# 1.net
KiCad netlist of a schematic drawn in Altium Designer
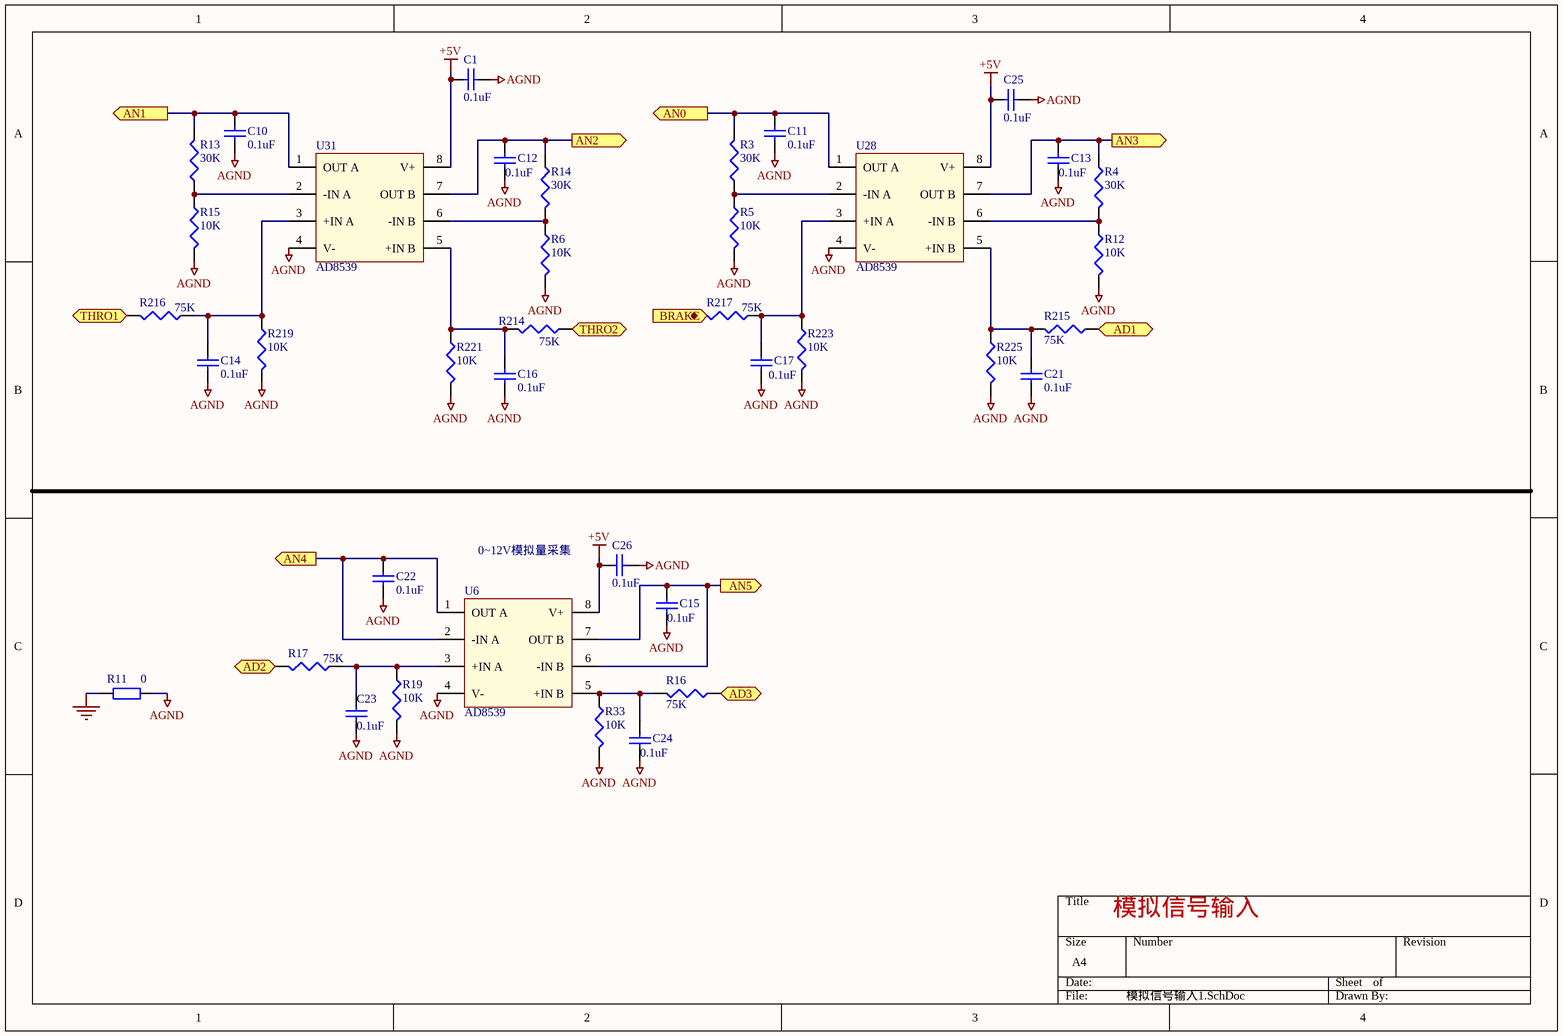
[diagram p0: 模拟信号输入1.SchDoc]

(export (version "E")
  (design (tool "Eeschema 10.0.6"))
  (components
    (comp (ref "C1")
      (value "0.1uF")
      (footprint "0603-L")
      (description "Ceramic, X7R, 100V, 10%, 0603")
      (fields (field (name "Comment") "Cap") (field (name "PUBLISHER") "Altium Limited"))
      (libsource (lib "Resistor") (part "CC0603KRX7R0BB104"))
    )
    (comp (ref "C10")
      (value "0.1uF")
      (footprint "0603-L")
      (description "Capacitor")
      (fields (field (name "Comment") "Cap") (field (name "PUBLISHER") "Altium Limited"))
      (libsource (lib "Miscellaneous Devices") (part "Cap"))
    )
    (comp (ref "C11")
      (value "0.1uF")
      (footprint "0603-L")
      (description "Capacitor")
      (fields (field (name "Comment") "Cap") (field (name "PUBLISHER") "Altium Limited"))
      (libsource (lib "Miscellaneous Devices") (part "Cap"))
    )
    (comp (ref "C12")
      (value "0.1uF")
      (footprint "0603-L")
      (description "Capacitor")
      (fields (field (name "Comment") "Cap") (field (name "PUBLISHER") "Altium Limited"))
      (libsource (lib "Miscellaneous Devices") (part "Cap"))
    )
    (comp (ref "C13")
      (value "0.1uF")
      (footprint "0603-L")
      (description "Capacitor")
      (fields (field (name "Comment") "Cap") (field (name "PUBLISHER") "Altium Limited"))
      (libsource (lib "Miscellaneous Devices") (part "Cap"))
    )
    (comp (ref "C14")
      (value "0.1uF")
      (footprint "0603-L")
      (description "Capacitor")
      (fields (field (name "Comment") "Cap") (field (name "PUBLISHER") "Altium Limited"))
      (libsource (lib "Miscellaneous Devices") (part "Cap"))
    )
    (comp (ref "C15")
      (value "0.1uF")
      (footprint "0603-L")
      (description "Capacitor")
      (fields (field (name "Comment") "Cap") (field (name "PUBLISHER") "Altium Limited"))
      (libsource (lib "Miscellaneous Devices") (part "Cap"))
    )
    (comp (ref "C16")
      (value "0.1uF")
      (footprint "0603-L")
      (description "Capacitor")
      (fields (field (name "Comment") "Cap") (field (name "PUBLISHER") "Altium Limited"))
      (libsource (lib "Miscellaneous Devices") (part "Cap"))
    )
    (comp (ref "C17")
      (value "0.1uF")
      (footprint "0603-L")
      (description "Capacitor")
      (fields (field (name "Comment") "Cap") (field (name "PUBLISHER") "Altium Limited"))
      (libsource (lib "Miscellaneous Devices") (part "Cap"))
    )
    (comp (ref "C21")
      (value "0.1uF")
      (footprint "0603-L")
      (description "Capacitor")
      (fields (field (name "Comment") "Cap") (field (name "PUBLISHER") "Altium Limited"))
      (libsource (lib "Miscellaneous Devices") (part "Cap"))
    )
    (comp (ref "C22")
      (value "0.1uF")
      (footprint "0603-L")
      (description "Capacitor")
      (fields (field (name "Comment") "Cap") (field (name "PUBLISHER") "Altium Limited"))
      (libsource (lib "Miscellaneous Devices") (part "Cap"))
    )
    (comp (ref "C23")
      (value "0.1uF")
      (footprint "0603-L")
      (description "Capacitor")
      (fields (field (name "Comment") "Cap") (field (name "PUBLISHER") "Altium Limited"))
      (libsource (lib "Miscellaneous Devices") (part "Cap"))
    )
    (comp (ref "C24")
      (value "0.1uF")
      (footprint "0603-L")
      (description "Capacitor")
      (fields (field (name "Comment") "Cap") (field (name "PUBLISHER") "Altium Limited"))
      (libsource (lib "Miscellaneous Devices") (part "Cap"))
    )
    (comp (ref "C25")
      (value "0.1uF")
      (footprint "0603-L")
      (description "Ceramic, X7R, 100V, 10%, 0603")
      (fields (field (name "Comment") "Cap") (field (name "PUBLISHER") "Altium Limited"))
      (libsource (lib "Resistor") (part "CC0603KRX7R0BB104"))
    )
    (comp (ref "C26")
      (value "0.1uF")
      (footprint "0603-L")
      (description "Ceramic, X7R, 100V, 10%, 0603")
      (fields (field (name "Comment") "Cap") (field (name "PUBLISHER") "Altium Limited"))
      (libsource (lib "Resistor") (part "CC0603KRX7R0BB104"))
    )
    (comp (ref "R3")
      (value "30K")
      (footprint "0603-L")
      (description "Resistor")
      (fields (field (name "Comment") "Res3") (field (name "PUBLISHER") "Altium Limited"))
      (libsource (lib "Miscellaneous Devices") (part "Res3"))
    )
    (comp (ref "R4")
      (value "30K")
      (footprint "0603-L")
      (description "Resistor")
      (fields (field (name "Comment") "Res3") (field (name "PUBLISHER") "Altium Limited"))
      (libsource (lib "Miscellaneous Devices") (part "Res3"))
    )
    (comp (ref "R5")
      (value "10K")
      (footprint "0603-L")
      (description "Resistor")
      (fields (field (name "Comment") "Res3") (field (name "PUBLISHER") "Altium Limited"))
      (libsource (lib "Miscellaneous Devices") (part "Res3"))
    )
    (comp (ref "R6")
      (value "10K")
      (footprint "0603-L")
      (description "Resistor")
      (fields (field (name "Comment") "Res3") (field (name "PUBLISHER") "Altium Limited"))
      (libsource (lib "Miscellaneous Devices") (part "Res3"))
    )
    (comp (ref "R11")
      (value "0")
      (footprint "RES1206")
      (description "Resistor")
      (fields (field (name "Comment") "Res2") (field (name "PUBLISHER") "Altium Limited"))
      (libsource (lib "Miscellaneous Devices") (part "Res2"))
    )
    (comp (ref "R12")
      (value "10K")
      (footprint "0603-L")
      (description "Resistor")
      (fields (field (name "Comment") "Res3") (field (name "PUBLISHER") "Altium Limited"))
      (libsource (lib "Miscellaneous Devices") (part "Res3"))
    )
    (comp (ref "R13")
      (value "30K")
      (footprint "0603-L")
      (description "Resistor")
      (fields (field (name "Comment") "Res3") (field (name "PUBLISHER") "Altium Limited"))
      (libsource (lib "Miscellaneous Devices") (part "Res3"))
    )
    (comp (ref "R14")
      (value "30K")
      (footprint "0603-L")
      (description "Resistor")
      (fields (field (name "Comment") "Res3") (field (name "PUBLISHER") "Altium Limited"))
      (libsource (lib "Miscellaneous Devices") (part "Res3"))
    )
    (comp (ref "R15")
      (value "10K")
      (footprint "0603-L")
      (description "Resistor")
      (fields (field (name "Comment") "Res3") (field (name "PUBLISHER") "Altium Limited"))
      (libsource (lib "Miscellaneous Devices") (part "Res3"))
    )
    (comp (ref "R16")
      (value "75K")
      (footprint "0603-L")
      (description "Resistor")
      (fields (field (name "Comment") "Res3") (field (name "PUBLISHER") "Altium Limited"))
      (libsource (lib "Miscellaneous Devices") (part "Res3"))
    )
    (comp (ref "R17")
      (value "75K")
      (footprint "0603-L")
      (description "Resistor")
      (fields (field (name "Comment") "Res3") (field (name "PUBLISHER") "Altium Limited"))
      (libsource (lib "Miscellaneous Devices") (part "Res3"))
    )
    (comp (ref "R19")
      (value "10K")
      (footprint "0603-L")
      (description "Resistor")
      (fields (field (name "Comment") "Res3") (field (name "PUBLISHER") "Altium Limited"))
      (libsource (lib "Miscellaneous Devices") (part "Res3"))
    )
    (comp (ref "R33")
      (value "10K")
      (footprint "0603-L")
      (description "Resistor")
      (fields (field (name "Comment") "Res3") (field (name "PUBLISHER") "Altium Limited"))
      (libsource (lib "Miscellaneous Devices") (part "Res3"))
    )
    (comp (ref "R214")
      (value "75K")
      (footprint "0603-L")
      (description "Resistor")
      (fields (field (name "Comment") "Res3") (field (name "PUBLISHER") "Altium Limited"))
      (libsource (lib "Miscellaneous Devices") (part "Res3"))
    )
    (comp (ref "R215")
      (value "75K")
      (footprint "0603-L")
      (description "Resistor")
      (fields (field (name "Comment") "Res3") (field (name "PUBLISHER") "Altium Limited"))
      (libsource (lib "Miscellaneous Devices") (part "Res3"))
    )
    (comp (ref "R216")
      (value "75K")
      (footprint "0603-L")
      (description "Resistor")
      (fields (field (name "Comment") "Res3") (field (name "PUBLISHER") "Altium Limited"))
      (libsource (lib "Miscellaneous Devices") (part "Res3"))
    )
    (comp (ref "R217")
      (value "75K")
      (footprint "0603-L")
      (description "Resistor")
      (fields (field (name "Comment") "Res3") (field (name "PUBLISHER") "Altium Limited"))
      (libsource (lib "Miscellaneous Devices") (part "Res3"))
    )
    (comp (ref "R219")
      (value "10K")
      (footprint "0603-L")
      (description "Resistor")
      (fields (field (name "Comment") "Res3") (field (name "PUBLISHER") "Altium Limited"))
      (libsource (lib "Miscellaneous Devices") (part "Res3"))
    )
    (comp (ref "R221")
      (value "10K")
      (footprint "0603-L")
      (description "Resistor")
      (fields (field (name "Comment") "Res3") (field (name "PUBLISHER") "Altium Limited"))
      (libsource (lib "Miscellaneous Devices") (part "Res3"))
    )
    (comp (ref "R223")
      (value "10K")
      (footprint "0603-L")
      (description "Resistor")
      (fields (field (name "Comment") "Res3") (field (name "PUBLISHER") "Altium Limited"))
      (libsource (lib "Miscellaneous Devices") (part "Res3"))
    )
    (comp (ref "R225")
      (value "10K")
      (footprint "0603-L")
      (description "Resistor")
      (fields (field (name "Comment") "Res3") (field (name "PUBLISHER") "Altium Limited"))
      (libsource (lib "Miscellaneous Devices") (part "Res3"))
    )
    (comp (ref "U6") (value "AD8539") (footprint "整车控制器:AD8539") (libsource (lib "整车控制器") (part "AD8539")))
    (comp (ref "U28") (value "AD8539") (footprint "整车控制器:AD8539") (libsource (lib "整车控制器") (part "AD8539")))
    (comp (ref "U31") (value "AD8539") (footprint "AD8539") (libsource (lib "整车控制器") (part "AD8539")))
  )
  (nets
    (net (code "1") (name "+5V") (class "Default")
      (node (ref "C1") (pin "2") (pinfunction "2_2") (pintype "passive"))
      (node (ref "C25") (pin "2") (pinfunction "2_2") (pintype "passive"))
      (node (ref "C26") (pin "2") (pinfunction "2_2") (pintype "passive"))
      (node (ref "U28") (pin "8") (pinfunction "V+_8") (pintype "passive"))
      (node (ref "U31") (pin "8") (pinfunction "V+_8") (pintype "passive"))
      (node (ref "U6") (pin "8") (pinfunction "V+_8") (pintype "passive"))
    )
    (net (code "2") (name "/AD1") (class "Default")
      (node (ref "R215") (pin "2") (pinfunction "2_2") (pintype "passive"))
    )
    (net (code "3") (name "/AD2") (class "Default")
      (node (ref "R17") (pin "2") (pinfunction "2_2") (pintype "passive"))
    )
    (net (code "4") (name "/AD3") (class "Default")
      (node (ref "R16") (pin "2") (pinfunction "2_2") (pintype "passive"))
    )
    (net (code "5") (name "/AN0") (class "Default")
      (node (ref "C11") (pin "2") (pinfunction "2_2") (pintype "passive"))
      (node (ref "R3") (pin "2") (pinfunction "2_2") (pintype "passive"))
      (node (ref "U28") (pin "1") (pinfunction "OUT_A_1") (pintype "passive"))
    )
    (net (code "6") (name "/AN1") (class "Default")
      (node (ref "C10") (pin "2") (pinfunction "2_2") (pintype "passive"))
      (node (ref "R13") (pin "2") (pinfunction "2_2") (pintype "passive"))
      (node (ref "U31") (pin "1") (pinfunction "OUT_A_1") (pintype "passive"))
    )
    (net (code "7") (name "/AN2") (class "Default")
      (node (ref "C12") (pin "1") (pinfunction "1_1") (pintype "passive"))
      (node (ref "R14") (pin "1") (pinfunction "1_1") (pintype "passive"))
      (node (ref "U31") (pin "7") (pinfunction "OUT_B_7") (pintype "passive"))
    )
    (net (code "8") (name "/AN3") (class "Default")
      (node (ref "C13") (pin "1") (pinfunction "1_1") (pintype "passive"))
      (node (ref "R4") (pin "1") (pinfunction "1_1") (pintype "passive"))
      (node (ref "U28") (pin "7") (pinfunction "OUT_B_7") (pintype "passive"))
    )
    (net (code "9") (name "/AN4") (class "Default")
      (node (ref "C22") (pin "2") (pinfunction "2_2") (pintype "passive"))
      (node (ref "U6") (pin "1") (pinfunction "OUT_A_1") (pintype "passive"))
      (node (ref "U6") (pin "2") (pinfunction "-IN_A_2") (pintype "passive"))
    )
    (net (code "10") (name "/AN5") (class "Default")
      (node (ref "C15") (pin "1") (pinfunction "1_1") (pintype "passive"))
      (node (ref "U6") (pin "6") (pinfunction "-IN_B_6") (pintype "passive"))
      (node (ref "U6") (pin "7") (pinfunction "OUT_B_7") (pintype "passive"))
    )
    (net (code "11") (name "/BRAKE") (class "Default")
      (node (ref "R217") (pin "2") (pinfunction "2_2") (pintype "passive"))
    )
    (net (code "12") (name "/THRO1") (class "Default")
      (node (ref "R216") (pin "2") (pinfunction "2_2") (pintype "passive"))
    )
    (net (code "13") (name "/THRO2") (class "Default")
      (node (ref "R214") (pin "2") (pinfunction "2_2") (pintype "passive"))
    )
    (net (code "14") (name "AGND") (class "Default")
      (node (ref "C1") (pin "1") (pinfunction "1_1") (pintype "passive"))
      (node (ref "C10") (pin "1") (pinfunction "1_1") (pintype "passive"))
      (node (ref "C11") (pin "1") (pinfunction "1_1") (pintype "passive"))
      (node (ref "C12") (pin "2") (pinfunction "2_2") (pintype "passive"))
      (node (ref "C13") (pin "2") (pinfunction "2_2") (pintype "passive"))
      (node (ref "C14") (pin "1") (pinfunction "1_1") (pintype "passive"))
      (node (ref "C15") (pin "2") (pinfunction "2_2") (pintype "passive"))
      (node (ref "C16") (pin "1") (pinfunction "1_1") (pintype "passive"))
      (node (ref "C17") (pin "1") (pinfunction "1_1") (pintype "passive"))
      (node (ref "C21") (pin "1") (pinfunction "1_1") (pintype "passive"))
      (node (ref "C22") (pin "1") (pinfunction "1_1") (pintype "passive"))
      (node (ref "C23") (pin "1") (pinfunction "1_1") (pintype "passive"))
      (node (ref "C24") (pin "1") (pinfunction "1_1") (pintype "passive"))
      (node (ref "C25") (pin "1") (pinfunction "1_1") (pintype "passive"))
      (node (ref "C26") (pin "1") (pinfunction "1_1") (pintype "passive"))
      (node (ref "R11") (pin "2") (pinfunction "2_2") (pintype "passive"))
      (node (ref "R12") (pin "2") (pinfunction "2_2") (pintype "passive"))
      (node (ref "R15") (pin "2") (pinfunction "2_2") (pintype "passive"))
      (node (ref "R19") (pin "2") (pinfunction "2_2") (pintype "passive"))
      (node (ref "R219") (pin "2") (pinfunction "2_2") (pintype "passive"))
      (node (ref "R221") (pin "2") (pinfunction "2_2") (pintype "passive"))
      (node (ref "R223") (pin "2") (pinfunction "2_2") (pintype "passive"))
      (node (ref "R225") (pin "2") (pinfunction "2_2") (pintype "passive"))
      (node (ref "R33") (pin "2") (pinfunction "2_2") (pintype "passive"))
      (node (ref "R5") (pin "2") (pinfunction "2_2") (pintype "passive"))
      (node (ref "R6") (pin "2") (pinfunction "2_2") (pintype "passive"))
      (node (ref "U28") (pin "4") (pinfunction "V-_4") (pintype "passive"))
      (node (ref "U31") (pin "4") (pinfunction "V-_4") (pintype "passive"))
      (node (ref "U6") (pin "4") (pinfunction "V-_4") (pintype "passive"))
    )
    (net (code "15") (name "GND") (class "Default")
      (node (ref "R11") (pin "1") (pinfunction "1_1") (pintype "passive"))
    )
    (net (code "16") (name "Net-(U6-+IN_A)") (class "Default")
      (node (ref "C23") (pin "2") (pinfunction "2_2") (pintype "passive"))
      (node (ref "R17") (pin "1") (pinfunction "1_1") (pintype "passive"))
      (node (ref "R19") (pin "1") (pinfunction "1_1") (pintype "passive"))
      (node (ref "U6") (pin "3") (pinfunction "+IN_A_3") (pintype "passive"))
    )
    (net (code "17") (name "Net-(U6-+IN_B)") (class "Default")
      (node (ref "C24") (pin "2") (pinfunction "2_2") (pintype "passive"))
      (node (ref "R16") (pin "1") (pinfunction "1_1") (pintype "passive"))
      (node (ref "R33") (pin "1") (pinfunction "1_1") (pintype "passive"))
      (node (ref "U6") (pin "5") (pinfunction "+IN_B_5") (pintype "passive"))
    )
    (net (code "18") (name "Net-(U28-+IN_A)") (class "Default")
      (node (ref "C17") (pin "2") (pinfunction "2_2") (pintype "passive"))
      (node (ref "R217") (pin "1") (pinfunction "1_1") (pintype "passive"))
      (node (ref "R223") (pin "1") (pinfunction "1_1") (pintype "passive"))
      (node (ref "U28") (pin "3") (pinfunction "+IN_A_3") (pintype "passive"))
    )
    (net (code "19") (name "Net-(U28-+IN_B)") (class "Default")
      (node (ref "C21") (pin "2") (pinfunction "2_2") (pintype "passive"))
      (node (ref "R215") (pin "1") (pinfunction "1_1") (pintype "passive"))
      (node (ref "R225") (pin "1") (pinfunction "1_1") (pintype "passive"))
      (node (ref "U28") (pin "5") (pinfunction "+IN_B_5") (pintype "passive"))
    )
    (net (code "20") (name "Net-(U28--IN_A)") (class "Default")
      (node (ref "R3") (pin "1") (pinfunction "1_1") (pintype "passive"))
      (node (ref "R5") (pin "1") (pinfunction "1_1") (pintype "passive"))
      (node (ref "U28") (pin "2") (pinfunction "-IN_A_2") (pintype "passive"))
    )
    (net (code "21") (name "Net-(U28--IN_B)") (class "Default")
      (node (ref "R12") (pin "1") (pinfunction "1_1") (pintype "passive"))
      (node (ref "R4") (pin "2") (pinfunction "2_2") (pintype "passive"))
      (node (ref "U28") (pin "6") (pinfunction "-IN_B_6") (pintype "passive"))
    )
    (net (code "22") (name "Net-(U31-+IN_A)") (class "Default")
      (node (ref "C14") (pin "2") (pinfunction "2_2") (pintype "passive"))
      (node (ref "R216") (pin "1") (pinfunction "1_1") (pintype "passive"))
      (node (ref "R219") (pin "1") (pinfunction "1_1") (pintype "passive"))
      (node (ref "U31") (pin "3") (pinfunction "+IN_A_3") (pintype "passive"))
    )
    (net (code "23") (name "Net-(U31-+IN_B)") (class "Default")
      (node (ref "C16") (pin "2") (pinfunction "2_2") (pintype "passive"))
      (node (ref "R214") (pin "1") (pinfunction "1_1") (pintype "passive"))
      (node (ref "R221") (pin "1") (pinfunction "1_1") (pintype "passive"))
      (node (ref "U31") (pin "5") (pinfunction "+IN_B_5") (pintype "passive"))
    )
    (net (code "24") (name "Net-(U31--IN_A)") (class "Default")
      (node (ref "R13") (pin "1") (pinfunction "1_1") (pintype "passive"))
      (node (ref "R15") (pin "1") (pinfunction "1_1") (pintype "passive"))
      (node (ref "U31") (pin "2") (pinfunction "-IN_A_2") (pintype "passive"))
    )
    (net (code "25") (name "Net-(U31--IN_B)") (class "Default")
      (node (ref "R14") (pin "2") (pinfunction "2_2") (pintype "passive"))
      (node (ref "R6") (pin "1") (pinfunction "1_1") (pintype "passive"))
      (node (ref "U31") (pin "6") (pinfunction "-IN_B_6") (pintype "passive"))
    )
  )
)
